# EasyDriver_v45.net
KiCad netlist of a schematic drawn in EAGLE
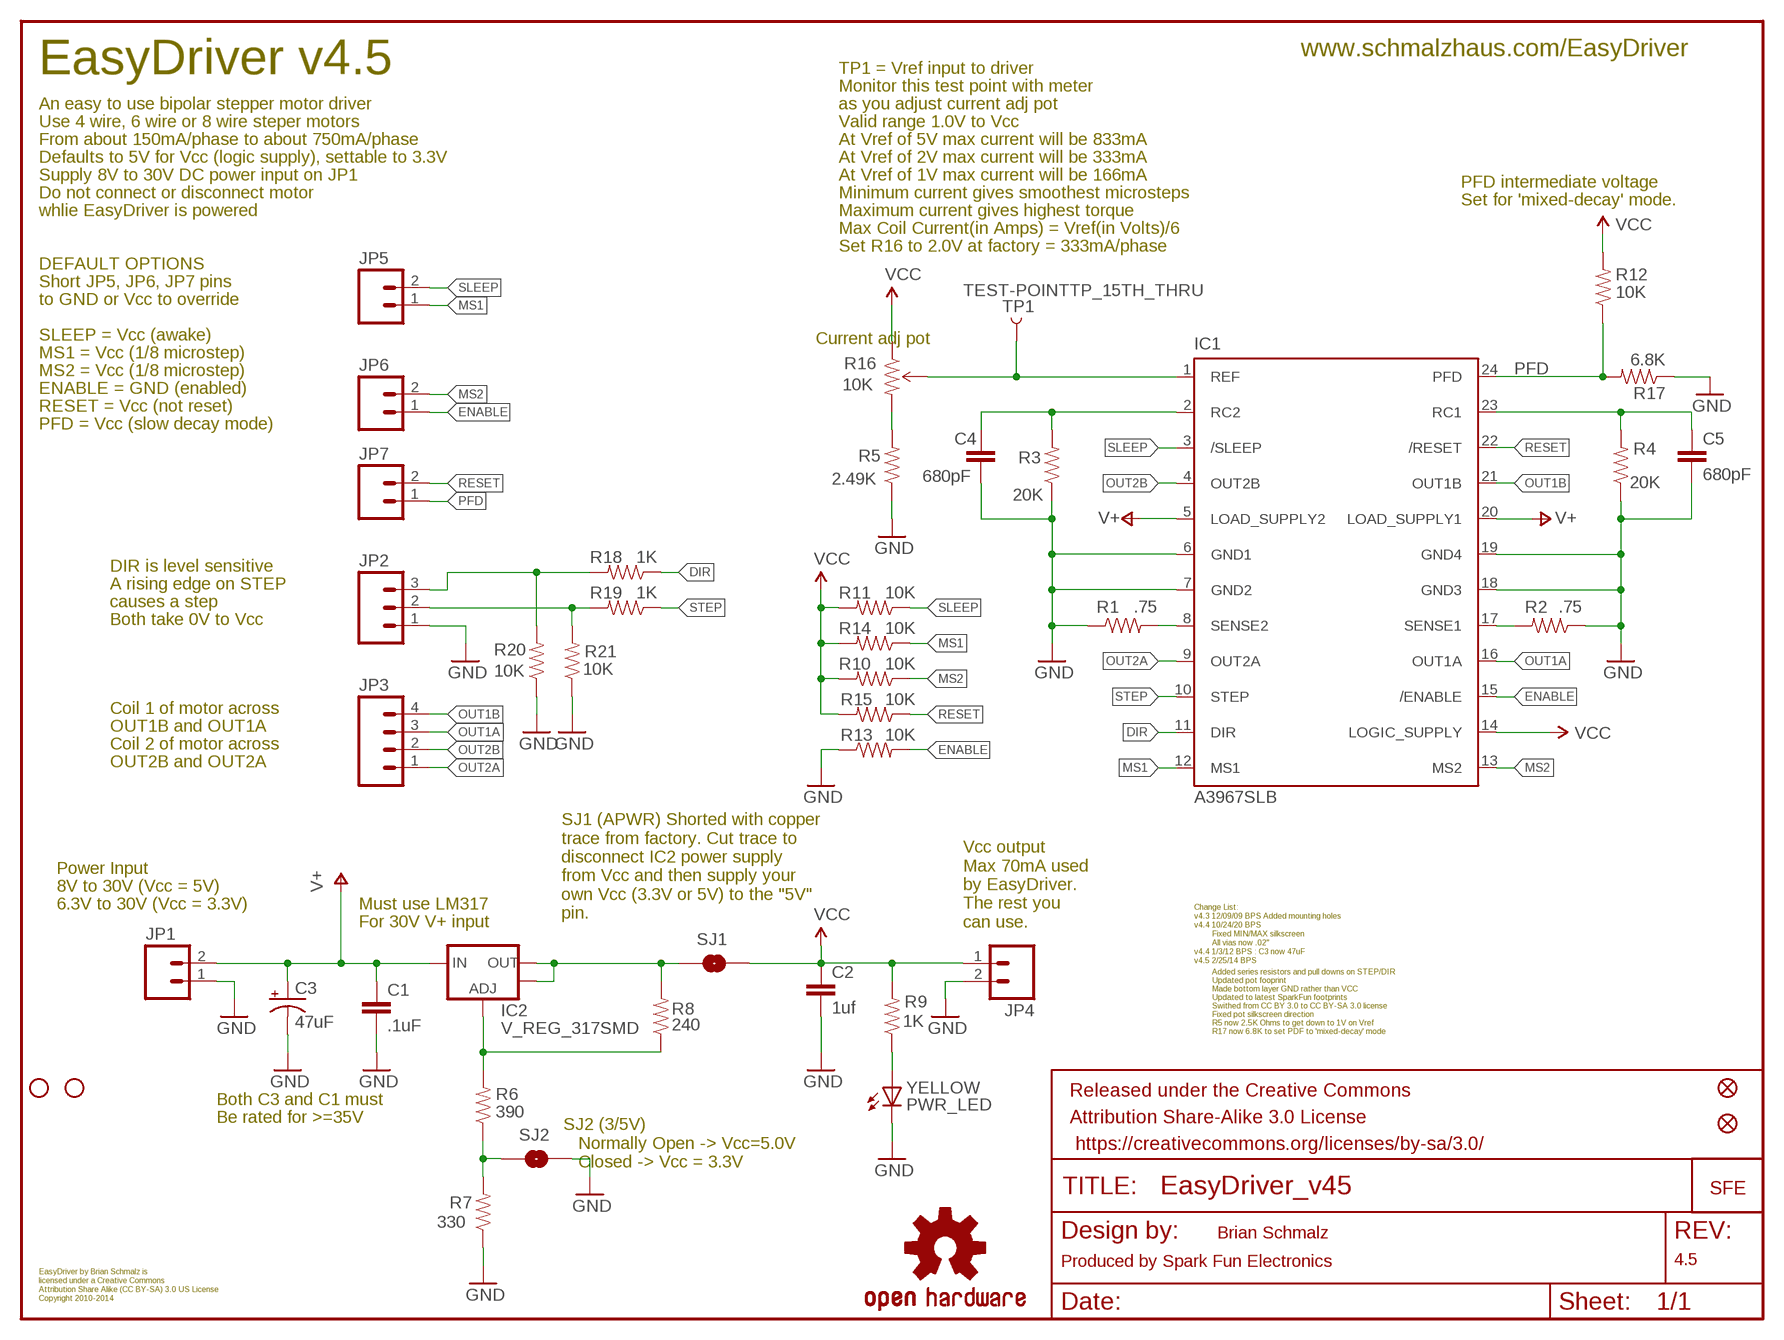
[diagram p0: schematic, sheet 1]

(export (version "E")
  (design (tool "Eeschema 10.0.6"))
  (components
    (comp (ref "C1")
      (value ".1uF")
      (footprint "eagle-import:0603-CAP")
      (libsource (lib "eagle-import") (part "CAP0603-CAP"))
    )
    (comp (ref "C2")
      (value "1uf")
      (footprint "eagle-import:0603-CAP")
      (libsource (lib "eagle-import") (part "CAP0603-CAP"))
    )
    (comp (ref "C3")
      (value "47uF")
      (footprint "eagle-import:PANASONIC_D")
      (libsource (lib "eagle-import") (part "CPOL-USD"))
    )
    (comp (ref "C4")
      (value "680pF")
      (footprint "eagle-import:0603-CAP")
      (libsource (lib "eagle-import") (part "CAP0603-CAP"))
    )
    (comp (ref "C5")
      (value "680pF")
      (footprint "eagle-import:0603-CAP")
      (libsource (lib "eagle-import") (part "CAP0603-CAP"))
    )
    (comp (ref "FID1")
      (value "FIDUCIAL1X2")
      (footprint "eagle-import:FIDUCIAL-1X2")
      (libsource (lib "eagle-import") (part "FIDUCIAL1X2"))
    )
    (comp (ref "FID2")
      (value "FIDUCIAL1X2")
      (footprint "eagle-import:FIDUCIAL-1X2")
      (libsource (lib "eagle-import") (part "FIDUCIAL1X2"))
    )
    (comp (ref "FRAME2")
      (value "FRAME-LETTER")
      (footprint "eagle-import:CREATIVE_COMMONS")
      (libsource (lib "eagle-import") (part "FRAME-LETTER"))
    )
    (comp (ref "IC1")
      (value "A3967SLB")
      (footprint "eagle-import:SO24W")
      (libsource (lib "eagle-import") (part "A3967SLB"))
    )
    (comp (ref "IC2")
      (value "V_REG_317SMD")
      (footprint "eagle-import:SOT223")
      (libsource (lib "eagle-import") (part "V_REG_317SMD"))
    )
    (comp (ref "JP1")
      (value "M021X02_NO_SILK")
      (footprint "eagle-import:1X02_NO_SILK")
      (libsource (lib "eagle-import") (part "M021X02_NO_SILK"))
    )
    (comp (ref "JP2")
      (value "M031X03_NO_SILK")
      (footprint "eagle-import:1X03_NO_SILK")
      (libsource (lib "eagle-import") (part "M031X03_NO_SILK"))
    )
    (comp (ref "JP3")
      (value "M041X04_NO_SILK")
      (footprint "eagle-import:1X04_NO_SILK")
      (libsource (lib "eagle-import") (part "M041X04_NO_SILK"))
    )
    (comp (ref "JP4")
      (value "M021X02_NO_SILK")
      (footprint "eagle-import:1X02_NO_SILK")
      (libsource (lib "eagle-import") (part "M021X02_NO_SILK"))
    )
    (comp (ref "JP5")
      (value "M021X02_NO_SILK")
      (footprint "eagle-import:1X02_NO_SILK")
      (libsource (lib "eagle-import") (part "M021X02_NO_SILK"))
    )
    (comp (ref "JP6")
      (value "M021X02_NO_SILK")
      (footprint "eagle-import:1X02_NO_SILK")
      (libsource (lib "eagle-import") (part "M021X02_NO_SILK"))
    )
    (comp (ref "JP7")
      (value "M021X02_NO_SILK")
      (footprint "eagle-import:1X02_NO_SILK")
      (libsource (lib "eagle-import") (part "M021X02_NO_SILK"))
    )
    (comp (ref "JP8")
      (value "STAND-OFF")
      (footprint "eagle-import:STAND-OFF")
      (libsource (lib "eagle-import") (part "STAND-OFF"))
    )
    (comp (ref "JP9")
      (value "STAND-OFF")
      (footprint "eagle-import:STAND-OFF")
      (libsource (lib "eagle-import") (part "STAND-OFF"))
    )
    (comp (ref "LOGO1")
      (value "OSHW-LOGOS")
      (footprint "eagle-import:OSHW-LOGO-S")
      (libsource (lib "eagle-import") (part "OSHW-LOGOS"))
    )
    (comp (ref "PWR_LED")
      (value "YELLOW")
      (footprint "eagle-import:LED-0603")
      (libsource (lib "eagle-import") (part "LED-YELLOW0603"))
    )
    (comp (ref "R1")
      (value ".75")
      (footprint "eagle-import:0805")
      (libsource (lib "eagle-import") (part "RESISTOR0805-RES"))
    )
    (comp (ref "R2")
      (value ".75")
      (footprint "eagle-import:0805")
      (libsource (lib "eagle-import") (part "RESISTOR0805-RES"))
    )
    (comp (ref "R3")
      (value "20K")
      (footprint "eagle-import:0603-RES")
      (libsource (lib "eagle-import") (part "RESISTOR0603"))
    )
    (comp (ref "R4")
      (value "20K")
      (footprint "eagle-import:0603-RES")
      (libsource (lib "eagle-import") (part "RESISTOR0603"))
    )
    (comp (ref "R5")
      (value "2.49K")
      (footprint "eagle-import:0603-RES")
      (libsource (lib "eagle-import") (part "RESISTOR0603"))
    )
    (comp (ref "R6")
      (value "390")
      (footprint "eagle-import:0603-RES")
      (libsource (lib "eagle-import") (part "RESISTOR0603"))
    )
    (comp (ref "R7")
      (value "330")
      (footprint "eagle-import:0603-RES")
      (libsource (lib "eagle-import") (part "RESISTOR0603"))
    )
    (comp (ref "R8")
      (value "240")
      (footprint "eagle-import:0603-RES")
      (libsource (lib "eagle-import") (part "RESISTOR0603"))
    )
    (comp (ref "R9")
      (value "1K")
      (footprint "eagle-import:0603-RES")
      (libsource (lib "eagle-import") (part "RESISTOR0603"))
    )
    (comp (ref "R10")
      (value "10K")
      (footprint "eagle-import:0603-RES")
      (libsource (lib "eagle-import") (part "RESISTOR0603"))
    )
    (comp (ref "R11")
      (value "10K")
      (footprint "eagle-import:0603-RES")
      (libsource (lib "eagle-import") (part "RESISTOR0603"))
    )
    (comp (ref "R12")
      (value "10K")
      (footprint "eagle-import:0603-RES")
      (libsource (lib "eagle-import") (part "RESISTOR0603"))
    )
    (comp (ref "R13")
      (value "10K")
      (footprint "eagle-import:0603-RES")
      (libsource (lib "eagle-import") (part "RESISTOR0603"))
    )
    (comp (ref "R14")
      (value "10K")
      (footprint "eagle-import:0603-RES")
      (libsource (lib "eagle-import") (part "RESISTOR0603"))
    )
    (comp (ref "R15")
      (value "10K")
      (footprint "eagle-import:0603-RES")
      (libsource (lib "eagle-import") (part "RESISTOR0603"))
    )
    (comp (ref "R16")
      (value "10K")
      (footprint "eagle-import:TRIMPOT-3MM-2")
      (libsource (lib "eagle-import") (part "TRIMPOT3MM-2"))
    )
    (comp (ref "R17")
      (value "6.8K")
      (footprint "eagle-import:0603-RES")
      (libsource (lib "eagle-import") (part "RESISTOR0603"))
    )
    (comp (ref "R18")
      (value "1K")
      (footprint "eagle-import:0603-RES")
      (libsource (lib "eagle-import") (part "RESISTOR0603"))
    )
    (comp (ref "R19")
      (value "1K")
      (footprint "eagle-import:0603-RES")
      (libsource (lib "eagle-import") (part "RESISTOR0603"))
    )
    (comp (ref "R20")
      (value "10K")
      (footprint "eagle-import:0603-RES")
      (libsource (lib "eagle-import") (part "RESISTOR0603"))
    )
    (comp (ref "R21")
      (value "10K")
      (footprint "eagle-import:0603-RES")
      (libsource (lib "eagle-import") (part "RESISTOR0603"))
    )
    (comp (ref "SJ1")
      (value "SOLDERJUMPERTRACE")
      (footprint "eagle-import:SJ_2S-TRACE")
      (libsource (lib "eagle-import") (part "SOLDERJUMPERTRACE"))
    )
    (comp (ref "SJ2")
      (value "SOLDERJUMPERNO")
      (footprint "eagle-import:SJ_2S-NO")
      (libsource (lib "eagle-import") (part "SOLDERJUMPERNO"))
    )
    (comp (ref "TP1")
      (value "TEST-POINTTP_15TH_THRU")
      (footprint "eagle-import:TP_15TH")
      (libsource (lib "eagle-import") (part "TEST-POINTTP_15TH_THRU"))
    )
    (comp (ref "U$2")
      (value "LOGO-SFENEW")
      (footprint "eagle-import:SFE-NEW-WEBLOGO")
      (libsource (lib "eagle-import") (part "LOGO-SFENEW"))
    )
  )
  (nets
    (net (code "1") (name "DIR") (class "Default")
      (node (ref "IC1") (pin "11") (pinfunction "DIR_11") (pintype "power_in"))
      (node (ref "R18") (pin "1") (pinfunction "1_1") (pintype "passive"))
    )
    (net (code "2") (name "ENABLE") (class "Default")
      (node (ref "IC1") (pin "15") (pinfunction "/ENABLE_15") (pintype "tri_state"))
      (node (ref "JP6") (pin "1") (pinfunction "1_1") (pintype "passive"))
      (node (ref "R13") (pin "2") (pinfunction "2_2") (pintype "passive"))
    )
    (net (code "3") (name "GND") (class "Default")
      (node (ref "C1") (pin "2") (pinfunction "2_2") (pintype "passive"))
      (node (ref "C2") (pin "2") (pinfunction "2_2") (pintype "passive"))
      (node (ref "C3") (pin "-") (pinfunction "-_-") (pintype "passive"))
      (node (ref "C4") (pin "2") (pinfunction "2_2") (pintype "passive"))
      (node (ref "C5") (pin "2") (pinfunction "2_2") (pintype "passive"))
      (node (ref "IC1") (pin "18") (pinfunction "GND3_18") (pintype "tri_state"))
      (node (ref "IC1") (pin "19") (pinfunction "GND4_19") (pintype "tri_state"))
      (node (ref "IC1") (pin "6") (pinfunction "GND1_6") (pintype "passive"))
      (node (ref "IC1") (pin "7") (pinfunction "GND2_7") (pintype "output"))
      (node (ref "JP1") (pin "1") (pinfunction "1_1") (pintype "passive"))
      (node (ref "JP2") (pin "1") (pinfunction "1_1") (pintype "passive"))
      (node (ref "JP4") (pin "2") (pinfunction "2_2") (pintype "passive"))
      (node (ref "PWR_LED") (pin "C") (pinfunction "C_C") (pintype "passive"))
      (node (ref "R1") (pin "1") (pinfunction "1_1") (pintype "passive"))
      (node (ref "R13") (pin "1") (pinfunction "1_1") (pintype "passive"))
      (node (ref "R17") (pin "1") (pinfunction "1_1") (pintype "passive"))
      (node (ref "R2") (pin "1") (pinfunction "1_1") (pintype "passive"))
      (node (ref "R20") (pin "1") (pinfunction "1_1") (pintype "passive"))
      (node (ref "R21") (pin "1") (pinfunction "1_1") (pintype "passive"))
      (node (ref "R3") (pin "1") (pinfunction "1_1") (pintype "passive"))
      (node (ref "R4") (pin "1") (pinfunction "1_1") (pintype "passive"))
      (node (ref "R5") (pin "1") (pinfunction "1_1") (pintype "passive"))
      (node (ref "R7") (pin "1") (pinfunction "1_1") (pintype "passive"))
      (node (ref "SJ2") (pin "2") (pinfunction "2_2") (pintype "passive"))
    )
    (net (code "4") (name "MS1") (class "Default")
      (node (ref "IC1") (pin "12") (pinfunction "MS1_12") (pintype "output"))
      (node (ref "JP5") (pin "1") (pinfunction "1_1") (pintype "passive"))
      (node (ref "R14") (pin "1") (pinfunction "1_1") (pintype "passive"))
    )
    (net (code "5") (name "MS2") (class "Default")
      (node (ref "IC1") (pin "13") (pinfunction "MS2_13") (pintype "tri_state"))
      (node (ref "JP6") (pin "2") (pinfunction "2_2") (pintype "passive"))
      (node (ref "R10") (pin "1") (pinfunction "1_1") (pintype "passive"))
    )
    (net (code "6") (name "Net-(IC1-RC1)") (class "Default")
      (node (ref "C5") (pin "1") (pinfunction "1_1") (pintype "passive"))
      (node (ref "IC1") (pin "23") (pinfunction "RC1_23") (pintype "tri_state"))
      (node (ref "R4") (pin "2") (pinfunction "2_2") (pintype "passive"))
    )
    (net (code "7") (name "Net-(IC1-RC2)") (class "Default")
      (node (ref "C4") (pin "1") (pinfunction "1_1") (pintype "passive"))
      (node (ref "IC1") (pin "2") (pinfunction "RC2_2") (pintype "input"))
      (node (ref "R3") (pin "2") (pinfunction "2_2") (pintype "passive"))
    )
    (net (code "8") (name "Net-(IC1-REF)") (class "Default")
      (node (ref "IC1") (pin "1") (pinfunction "REF_1") (pintype "power_in"))
      (node (ref "R16") (pin "2") (pinfunction "WIPER_2") (pintype "passive"))
      (node (ref "TP1") (pin "P$1") (pinfunction "1_P$1") (pintype "bidirectional"))
    )
    (net (code "9") (name "Net-(IC1-SENSE1)") (class "Default")
      (node (ref "IC1") (pin "17") (pinfunction "SENSE1_17") (pintype "tri_state"))
      (node (ref "R2") (pin "2") (pinfunction "2_2") (pintype "passive"))
    )
    (net (code "10") (name "Net-(IC1-SENSE2)") (class "Default")
      (node (ref "IC1") (pin "8") (pinfunction "SENSE2_8") (pintype "input"))
      (node (ref "R1") (pin "2") (pinfunction "2_2") (pintype "passive"))
    )
    (net (code "11") (name "Net-(IC2-ADJ)") (class "Default")
      (node (ref "IC2") (pin "1") (pinfunction "ADJ_1") (pintype "input"))
      (node (ref "R6") (pin "2") (pinfunction "2_2") (pintype "passive"))
      (node (ref "R8") (pin "1") (pinfunction "1_1") (pintype "passive"))
    )
    (net (code "12") (name "Net-(IC2-OUT-Pad2)") (class "Default")
      (node (ref "IC2") (pin "2") (pinfunction "OUT_2") (pintype "output"))
      (node (ref "IC2") (pin "4") (pinfunction "OUT_4") (pintype "output"))
      (node (ref "R8") (pin "2") (pinfunction "2_2") (pintype "passive"))
      (node (ref "SJ1") (pin "1") (pinfunction "1_1") (pintype "passive"))
    )
    (net (code "13") (name "Net-(JP2-Pad2)") (class "Default")
      (node (ref "JP2") (pin "2") (pinfunction "2_2") (pintype "passive"))
      (node (ref "R19") (pin "2") (pinfunction "2_2") (pintype "passive"))
      (node (ref "R21") (pin "2") (pinfunction "2_2") (pintype "passive"))
    )
    (net (code "14") (name "Net-(JP2-Pad3)") (class "Default")
      (node (ref "JP2") (pin "3") (pinfunction "3_3") (pintype "passive"))
      (node (ref "R18") (pin "2") (pinfunction "2_2") (pintype "passive"))
      (node (ref "R20") (pin "2") (pinfunction "2_2") (pintype "passive"))
    )
    (net (code "15") (name "Net-(PWR_LED-PadA)") (class "Default")
      (node (ref "PWR_LED") (pin "A") (pinfunction "A_A") (pintype "passive"))
      (node (ref "R9") (pin "1") (pinfunction "1_1") (pintype "passive"))
    )
    (net (code "16") (name "Net-(R6-Pad1)") (class "Default")
      (node (ref "R6") (pin "1") (pinfunction "1_1") (pintype "passive"))
      (node (ref "R7") (pin "2") (pinfunction "2_2") (pintype "passive"))
      (node (ref "SJ2") (pin "1") (pinfunction "1_1") (pintype "passive"))
    )
    (net (code "17") (name "Net-(R16-CW)") (class "Default")
      (node (ref "R16") (pin "3") (pinfunction "CW_3") (pintype "passive"))
      (node (ref "R5") (pin "2") (pinfunction "2_2") (pintype "passive"))
    )
    (net (code "18") (name "OUT1A") (class "Default")
      (node (ref "IC1") (pin "16") (pinfunction "OUT1A_16") (pintype "tri_state"))
      (node (ref "JP3") (pin "3") (pinfunction "3_3") (pintype "passive"))
    )
    (net (code "19") (name "OUT1B") (class "Default")
      (node (ref "IC1") (pin "21") (pinfunction "OUT1B_21") (pintype "tri_state"))
      (node (ref "JP3") (pin "4") (pinfunction "4_4") (pintype "passive"))
    )
    (net (code "20") (name "OUT2A") (class "Default")
      (node (ref "IC1") (pin "9") (pinfunction "OUT2A_9") (pintype "power_in"))
      (node (ref "JP3") (pin "1") (pinfunction "1_1") (pintype "passive"))
    )
    (net (code "21") (name "OUT2B") (class "Default")
      (node (ref "IC1") (pin "4") (pinfunction "OUT2B_4") (pintype "passive"))
      (node (ref "JP3") (pin "2") (pinfunction "2_2") (pintype "passive"))
    )
    (net (code "22") (name "PFD") (class "Default")
      (node (ref "IC1") (pin "24") (pinfunction "PFD_24") (pintype "tri_state"))
      (node (ref "JP7") (pin "1") (pinfunction "1_1") (pintype "passive"))
      (node (ref "R12") (pin "1") (pinfunction "1_1") (pintype "passive"))
      (node (ref "R17") (pin "2") (pinfunction "2_2") (pintype "passive"))
    )
    (net (code "23") (name "RESET") (class "Default")
      (node (ref "IC1") (pin "22") (pinfunction "/RESET_22") (pintype "tri_state"))
      (node (ref "JP7") (pin "2") (pinfunction "2_2") (pintype "passive"))
      (node (ref "R15") (pin "1") (pinfunction "1_1") (pintype "passive"))
    )
    (net (code "24") (name "SLEEP") (class "Default")
      (node (ref "IC1") (pin "3") (pinfunction "/SLEEP_3") (pintype "passive"))
      (node (ref "JP5") (pin "2") (pinfunction "2_2") (pintype "passive"))
      (node (ref "R11") (pin "1") (pinfunction "1_1") (pintype "passive"))
    )
    (net (code "25") (name "STEP") (class "Default")
      (node (ref "IC1") (pin "10") (pinfunction "STEP_10") (pintype "power_in"))
      (node (ref "R19") (pin "1") (pinfunction "1_1") (pintype "passive"))
    )
    (net (code "26") (name "V+") (class "Default")
      (node (ref "C1") (pin "1") (pinfunction "1_1") (pintype "passive"))
      (node (ref "C3") (pin "+") (pinfunction "+_+") (pintype "passive"))
      (node (ref "IC1") (pin "20") (pinfunction "LOAD_SUPPLY1_20") (pintype "tri_state"))
      (node (ref "IC1") (pin "5") (pinfunction "LOAD_SUPPLY2_5") (pintype "passive"))
      (node (ref "IC2") (pin "3") (pinfunction "IN_3") (pintype "input"))
      (node (ref "JP1") (pin "2") (pinfunction "2_2") (pintype "passive"))
    )
    (net (code "27") (name "VCC") (class "Default")
      (node (ref "C2") (pin "1") (pinfunction "1_1") (pintype "passive"))
      (node (ref "IC1") (pin "14") (pinfunction "LOGIC_SUPPLY_14") (pintype "tri_state"))
      (node (ref "JP4") (pin "1") (pinfunction "1_1") (pintype "passive"))
      (node (ref "R10") (pin "2") (pinfunction "2_2") (pintype "passive"))
      (node (ref "R11") (pin "2") (pinfunction "2_2") (pintype "passive"))
      (node (ref "R12") (pin "2") (pinfunction "2_2") (pintype "passive"))
      (node (ref "R14") (pin "2") (pinfunction "2_2") (pintype "passive"))
      (node (ref "R15") (pin "2") (pinfunction "2_2") (pintype "passive"))
      (node (ref "R16") (pin "1") (pinfunction "CCW_1") (pintype "passive"))
      (node (ref "R9") (pin "2") (pinfunction "2_2") (pintype "passive"))
      (node (ref "SJ1") (pin "2") (pinfunction "2_2") (pintype "passive"))
    )
  )
)
